# Heater_Thermometer.net
KiCad netlist of a schematic drawn in Altium Designer
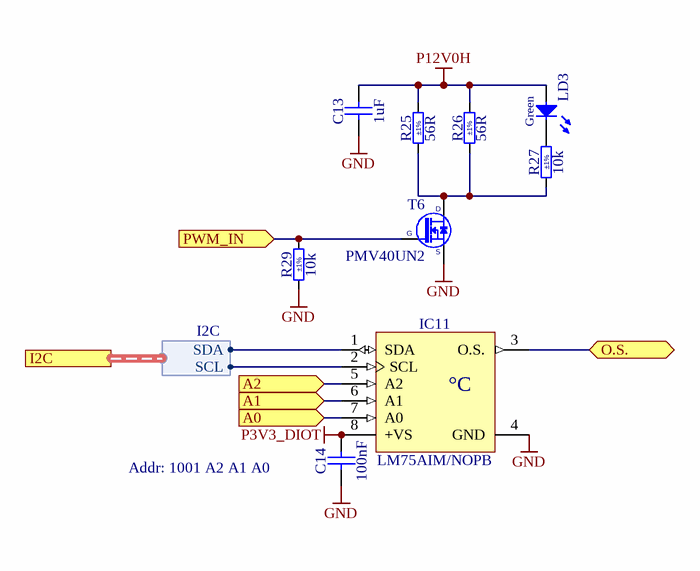
[diagram p0: Heater_Thermometer.SchDoc]

(export (version "E")
  (design (tool "Eeschema 10.0.6"))
  (components
    (comp (ref "C13")
      (value "1uF")
      (footprint "CAPC1608X87N")
      (description "Non-polarised capacitor")
      (fields
        (field (name "PART NUMBER") "CC0603_1UF_25V_10%_X7R")
        (field (name "VOLTAGE") "25V")
        (field (name "AUTHOR") "CERN DEM JLC")
      )
      (libsource (lib "Capacitors") (part "Capacitor - non polarized"))
    )
    (comp (ref "C14")
      (value "100nF")
      (footprint "CAPC1005X55N")
      (description "Non-polarised capacitor")
      (fields
        (field (name "PART NUMBER") "CC0402_100NF_50V_10%_X7R")
        (field (name "VOLTAGE") "50V")
        (field (name "AUTHOR") "CERN DEM MR")
      )
      (libsource (lib "Capacitors") (part "Capacitor - non polarized"))
    )
    (comp (ref "IC11")
      (value "LM75AIM/NOPB")
      (footprint "SOIC127P600X175-8N")
      (description "Digital Temperature Sensor and Thermal Watchdog with Two-Wire Interface")
      (fields
        (field (name "MANUFACTURER") "TEXAS INSTRUMENTS")
        (field (name "MANUFACTURER PART NUMBER") "LM75AIM")
        (field (name "AUTHOR") "CERN DEM JLC")
      )
      (libsource (lib "ICs And Semiconductors") (part "LM75"))
    )
    (comp (ref "LD3")
      (value "Green")
      (footprint "LED_AVAGO_HSME-C120")
      (description "LED Green 1C 2A")
      (fields
        (field (name "PART NUMBER") "LED_AVAGO_HSME-C120")
        (field (name "MANUFACTURER") "AVAGO TECHNOLOGIES")
        (field (name "AUTHOR") "CERN DEM JMW")
      )
      (libsource (lib "ICs And Semiconductors") (part "LED Green 1C 2A"))
    )
    (comp (ref "R25")
      (value "56R")
      (footprint "RES_TYCO_3522")
      (description "Resistor - 1%")
      (fields
        (field (name "PART NUMBER") "R2512_56R_1%_3W_200PPM")
        (field (name "POWER") "3W")
        (field (name "TOLERANCE") "±1%")
        (field (name "AUTHOR") "GK")
      )
      (libsource (lib "Passives_RC") (part "R2512_56R_1%_3W_200PPM"))
    )
    (comp (ref "R26")
      (value "56R")
      (footprint "RES_TYCO_3522")
      (description "Resistor - 1%")
      (fields
        (field (name "PART NUMBER") "R2512_56R_1%_3W_200PPM")
        (field (name "POWER") "3W")
        (field (name "TOLERANCE") "±1%")
        (field (name "AUTHOR") "GK")
      )
      (libsource (lib "Passives_RC") (part "R2512_56R_1%_3W_200PPM"))
    )
    (comp (ref "R27")
      (value "10k")
      (footprint "RESC1005X40N")
      (description "Resistor - 1%")
      (fields
        (field (name "TOLERANCE") "±1%")
        (field (name "PART NUMBER") "R0402_10K_1%_0.0625W_100PPM")
        (field (name "POWER") "0.0625W")
        (field (name "AUTHOR") "CERN DEM JLC")
      )
      (libsource (lib "Resistors") (part "Resistor - 1%"))
    )
    (comp (ref "R29")
      (value "10k")
      (footprint "RESC1005X40N")
      (description "Resistor - 1%")
      (fields
        (field (name "TOLERANCE") "±1%")
        (field (name "PART NUMBER") "R0402_10K_1%_0.0625W_100PPM")
        (field (name "POWER") "0.0625W")
        (field (name "AUTHOR") "CERN DEM JLC")
      )
      (libsource (lib "Resistors") (part "Resistor - 1%"))
    )
    (comp (ref "T6")
      (value "PMV40UN2")
      (footprint "SOT95P230X110-3N")
      (description "N-CHANNEL MOSFET WITH DIODE")
      (fields (field (name "MANUFACTURER") "NEXPERIA") (field (name "AUTHOR") "CERN DEM BC"))
      (libsource (lib "ICs And Semiconductors") (part "N-MOSFET-D 1G 2S 3D"))
    )
  )
  (nets
    (net (code "2") (name "/A0") (class "Default")
      (node (ref "IC11") (pin "7") (pinfunction "A0_7") (pintype "input"))
    )
    (net (code "3") (name "/A1") (class "Default")
      (node (ref "IC11") (pin "6") (pinfunction "A1_6") (pintype "input"))
    )
    (net (code "4") (name "/A2") (class "Default")
      (node (ref "IC11") (pin "5") (pinfunction "A2_5") (pintype "input"))
    )
    (net (code "5") (name "/O.S.") (class "Default")
      (node (ref "IC11") (pin "3") (pinfunction "O.S._3") (pintype "output"))
    )
    (net (code "6") (name "/PWM_IN") (class "Default")
      (node (ref "R29") (pin "2") (pinfunction "2_2") (pintype "passive"))
      (node (ref "T6") (pin "1") (pinfunction "G_1") (pintype "passive"))
    )
    (net (code "7") (name "/SCL") (class "Default")
      (node (ref "IC11") (pin "2") (pinfunction "SCL_2") (pintype "input"))
    )
    (net (code "8") (name "/SDA") (class "Default")
      (node (ref "IC11") (pin "1") (pinfunction "SDA_1") (pintype "bidirectional"))
    )
    (net (code "10") (name "GND") (class "Default")
      (node (ref "C13") (pin "1") (pinfunction "1_1") (pintype "passive"))
      (node (ref "C14") (pin "1") (pinfunction "1_1") (pintype "passive"))
      (node (ref "IC11") (pin "4") (pinfunction "GND_4") (pintype "power_in"))
      (node (ref "R29") (pin "1") (pinfunction "1_1") (pintype "passive"))
      (node (ref "T6") (pin "2") (pinfunction "S_2") (pintype "passive"))
    )
    (net (code "11") (name "Net-(LD3-C)") (class "Default")
      (node (ref "LD3") (pin "1") (pinfunction "C_1") (pintype "passive"))
      (node (ref "R27") (pin "2") (pinfunction "2_2") (pintype "passive"))
    )
    (net (code "12") (name "Net-(T6-D)") (class "Default")
      (node (ref "R25") (pin "1") (pinfunction "1_1") (pintype "passive"))
      (node (ref "R26") (pin "1") (pinfunction "1_1") (pintype "passive"))
      (node (ref "R27") (pin "1") (pinfunction "1_1") (pintype "passive"))
      (node (ref "T6") (pin "3") (pinfunction "D_3") (pintype "passive"))
    )
    (net (code "13") (name "P3V3_DIOT") (class "Default")
      (node (ref "C14") (pin "2") (pinfunction "2_2") (pintype "passive"))
      (node (ref "IC11") (pin "8") (pinfunction "+VS_8") (pintype "power_in"))
    )
    (net (code "14") (name "P12V0H") (class "Default")
      (node (ref "C13") (pin "2") (pinfunction "2_2") (pintype "passive"))
      (node (ref "LD3") (pin "2") (pinfunction "A_2") (pintype "passive"))
      (node (ref "R25") (pin "2") (pinfunction "2_2") (pintype "passive"))
      (node (ref "R26") (pin "2") (pinfunction "2_2") (pintype "passive"))
    )
  )
)
